# 1x9x1_2.net
KiCad netlist of a schematic drawn in Altium Designer
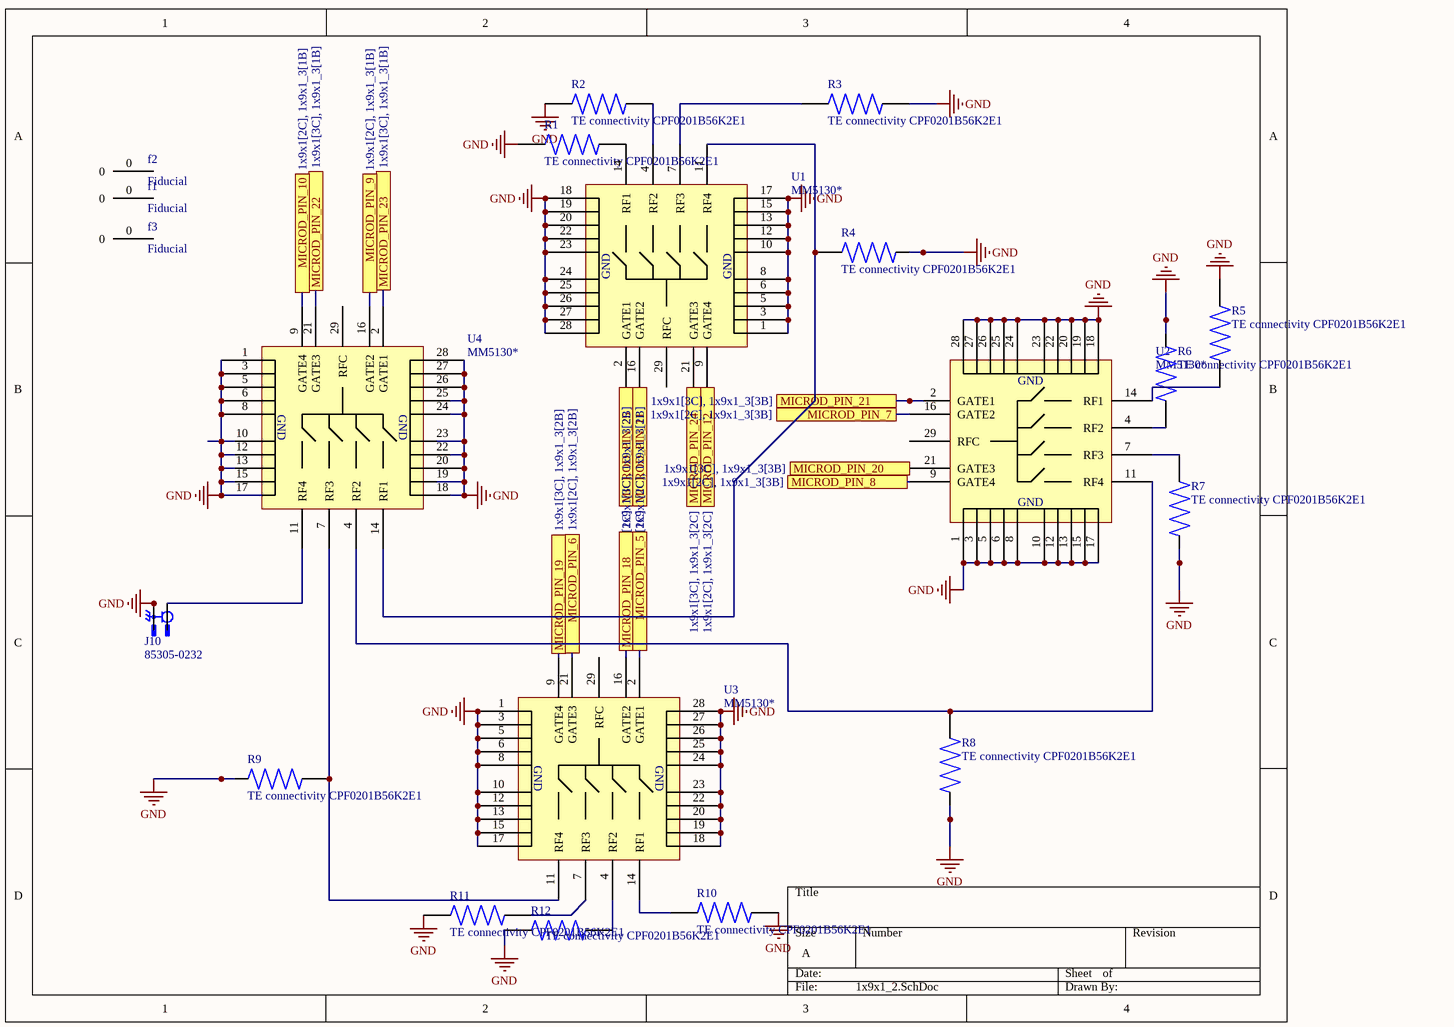
[diagram p0: 1x9x1_2.SchDoc]

(export (version "E")
  (design (tool "Eeschema 10.0.6"))
  (components
    (comp (ref "f1") (value "Fiducial") (footprint "fiducial") (libsource (lib "Fiducial") (part "Fiducial")))
    (comp (ref "f2") (value "Fiducial") (footprint "fiducial") (libsource (lib "Fiducial") (part "Fiducial")))
    (comp (ref "f3") (value "Fiducial") (footprint "fiducial") (libsource (lib "Fiducial") (part "Fiducial")))
    (comp (ref "J10")
      (value "85305-0232")
      (footprint "MOLEX_85305-0232")
      (description "SMP Connector Plug, Male Pin 50Ohm Surface Mount Solder")
      (fields (field (name "MP") "853050232") (field (name "MF") "Molex"))
      (libsource (lib "85305-0232") (part "85305-0232"))
    )
    (comp (ref "R1")
      (value "TE connectivity CPF0201B56K2E1")
      (footprint "0201-resistor")
      (description "CPF 0201 56K2 0.1% 25PPM 1K RL")
      (fields (field (name "MP") "ERJ1GN0R00C") (field (name "MFGR PART NO.") "CPF0201B56K2E1"))
      (libsource (lib "SchlibLafe") (part "TE connectivity CPF0201B56K2E1"))
    )
    (comp (ref "R2")
      (value "TE connectivity CPF0201B56K2E1")
      (footprint "0201-resistor")
      (description "CPF 0201 56K2 0.1% 25PPM 1K RL")
      (fields (field (name "MP") "ERJ1GN0R00C") (field (name "MFGR PART NO.") "CPF0201B56K2E1"))
      (libsource (lib "SchlibLafe") (part "TE connectivity CPF0201B56K2E1"))
    )
    (comp (ref "R3")
      (value "TE connectivity CPF0201B56K2E1")
      (footprint "0201-resistor")
      (description "CPF 0201 56K2 0.1% 25PPM 1K RL")
      (fields (field (name "MP") "ERJ1GN0R00C") (field (name "MFGR PART NO.") "CPF0201B56K2E1"))
      (libsource (lib "SchlibLafe") (part "TE connectivity CPF0201B56K2E1"))
    )
    (comp (ref "R4")
      (value "TE connectivity CPF0201B56K2E1")
      (footprint "0201-resistor")
      (description "CPF 0201 56K2 0.1% 25PPM 1K RL")
      (fields (field (name "MP") "ERJ1GN0R00C") (field (name "MFGR PART NO.") "CPF0201B56K2E1"))
      (libsource (lib "SchlibLafe") (part "TE connectivity CPF0201B56K2E1"))
    )
    (comp (ref "R5")
      (value "TE connectivity CPF0201B56K2E1")
      (footprint "0201-resistor")
      (description "CPF 0201 56K2 0.1% 25PPM 1K RL")
      (fields (field (name "MP") "ERJ1GN0R00C") (field (name "MFGR PART NO.") "CPF0201B56K2E1"))
      (libsource (lib "SchlibLafe") (part "TE connectivity CPF0201B56K2E1"))
    )
    (comp (ref "R6")
      (value "TE connectivity CPF0201B56K2E1")
      (footprint "0201-resistor")
      (description "CPF 0201 56K2 0.1% 25PPM 1K RL")
      (fields (field (name "MP") "ERJ1GN0R00C") (field (name "MFGR PART NO.") "CPF0201B56K2E1"))
      (libsource (lib "SchlibLafe") (part "TE connectivity CPF0201B56K2E1"))
    )
    (comp (ref "R7")
      (value "TE connectivity CPF0201B56K2E1")
      (footprint "0201-resistor")
      (description "CPF 0201 56K2 0.1% 25PPM 1K RL")
      (fields (field (name "MP") "ERJ1GN0R00C") (field (name "MFGR PART NO.") "CPF0201B56K2E1"))
      (libsource (lib "SchlibLafe") (part "TE connectivity CPF0201B56K2E1"))
    )
    (comp (ref "R8")
      (value "TE connectivity CPF0201B56K2E1")
      (footprint "0201-resistor")
      (description "CPF 0201 56K2 0.1% 25PPM 1K RL")
      (fields (field (name "MP") "ERJ1GN0R00C") (field (name "MFGR PART NO.") "CPF0201B56K2E1"))
      (libsource (lib "SchlibLafe") (part "TE connectivity CPF0201B56K2E1"))
    )
    (comp (ref "R9")
      (value "TE connectivity CPF0201B56K2E1")
      (footprint "0201-resistor")
      (description "CPF 0201 56K2 0.1% 25PPM 1K RL")
      (fields (field (name "MP") "ERJ1GN0R00C") (field (name "MFGR PART NO.") "CPF0201B56K2E1"))
      (libsource (lib "SchlibLafe") (part "TE connectivity CPF0201B56K2E1"))
    )
    (comp (ref "R10")
      (value "TE connectivity CPF0201B56K2E1")
      (footprint "0201-resistor")
      (description "CPF 0201 56K2 0.1% 25PPM 1K RL")
      (fields (field (name "MP") "ERJ1GN0R00C") (field (name "MFGR PART NO.") "CPF0201B56K2E1"))
      (libsource (lib "SchlibLafe") (part "TE connectivity CPF0201B56K2E1"))
    )
    (comp (ref "R11")
      (value "TE connectivity CPF0201B56K2E1")
      (footprint "0201-resistor")
      (description "CPF 0201 56K2 0.1% 25PPM 1K RL")
      (fields (field (name "MP") "ERJ1GN0R00C") (field (name "MFGR PART NO.") "CPF0201B56K2E1"))
      (libsource (lib "SchlibLafe") (part "TE connectivity CPF0201B56K2E1"))
    )
    (comp (ref "R12")
      (value "TE connectivity CPF0201B56K2E1")
      (footprint "0201-resistor")
      (description "CPF 0201 56K2 0.1% 25PPM 1K RL")
      (fields (field (name "MP") "ERJ1GN0R00C") (field (name "MFGR PART NO.") "CPF0201B56K2E1"))
      (libsource (lib "SchlibLafe") (part "TE connectivity CPF0201B56K2E1"))
    )
    (comp (ref "U1")
      (value "MM5130*")
      (footprint "MM5130-NORM_PCB_NOFLOOD")
      (description "High power SP4T MEMs switch")
      (libsource (lib "") (part "IC-MM5130_1"))
    )
    (comp (ref "U2")
      (value "MM5130*")
      (footprint "MM5130-NORM_PCB_NOFLOOD")
      (description "High power SP4T MEMs switch")
      (libsource (lib "") (part "IC-MM5130_2"))
    )
    (comp (ref "U3")
      (value "MM5130*")
      (footprint "MM5130-NORM_PCB_NOFLOOD")
      (description "High power SP4T MEMs switch")
      (libsource (lib "MM5130_SCHSYM") (part "IC-MM5130"))
    )
    (comp (ref "U4")
      (value "MM5130*")
      (footprint "MM5130-NORM_PCB_NOFLOOD")
      (description "High power SP4T MEMs switch")
      (libsource (lib "MM5130_SCHSYM") (part "IC-MM5130"))
    )
  )
  (nets
    (net (code "1") (name "/MICROD_PIN_5") (class "Default")
      (node (ref "U3") (pin "2") (pinfunction "GATE1_2") (pintype "passive"))
    )
    (net (code "2") (name "/MICROD_PIN_6") (class "Default")
      (node (ref "U3") (pin "21") (pinfunction "GATE3_21") (pintype "passive"))
    )
    (net (code "3") (name "/MICROD_PIN_7") (class "Default")
      (node (ref "U2") (pin "16") (pinfunction "GATE2_16") (pintype "passive"))
    )
    (net (code "4") (name "/MICROD_PIN_8") (class "Default")
      (node (ref "U2") (pin "9") (pinfunction "GATE4_9") (pintype "passive"))
    )
    (net (code "5") (name "/MICROD_PIN_9") (class "Default")
      (node (ref "U4") (pin "16") (pinfunction "GATE2_16") (pintype "passive"))
    )
    (net (code "6") (name "/MICROD_PIN_10") (class "Default")
      (node (ref "U4") (pin "9") (pinfunction "GATE4_9") (pintype "passive"))
    )
    (net (code "7") (name "/MICROD_PIN_11") (class "Default")
      (node (ref "U1") (pin "16") (pinfunction "GATE2_16") (pintype "passive"))
    )
    (net (code "8") (name "/MICROD_PIN_12") (class "Default")
      (node (ref "U1") (pin "9") (pinfunction "GATE4_9") (pintype "passive"))
    )
    (net (code "9") (name "/MICROD_PIN_18") (class "Default")
      (node (ref "U3") (pin "16") (pinfunction "GATE2_16") (pintype "passive"))
    )
    (net (code "10") (name "/MICROD_PIN_19") (class "Default")
      (node (ref "U3") (pin "9") (pinfunction "GATE4_9") (pintype "passive"))
    )
    (net (code "11") (name "/MICROD_PIN_20") (class "Default")
      (node (ref "U2") (pin "21") (pinfunction "GATE3_21") (pintype "passive"))
    )
    (net (code "12") (name "/MICROD_PIN_21") (class "Default")
      (node (ref "U2") (pin "2") (pinfunction "GATE1_2") (pintype "passive"))
    )
    (net (code "13") (name "/MICROD_PIN_22") (class "Default")
      (node (ref "U4") (pin "21") (pinfunction "GATE3_21") (pintype "passive"))
    )
    (net (code "14") (name "/MICROD_PIN_23") (class "Default")
      (node (ref "U4") (pin "2") (pinfunction "GATE1_2") (pintype "passive"))
    )
    (net (code "15") (name "/MICROD_PIN_24") (class "Default")
      (node (ref "U1") (pin "21") (pinfunction "GATE3_21") (pintype "passive"))
    )
    (net (code "16") (name "/MICROD_PIN_25") (class "Default")
      (node (ref "U1") (pin "2") (pinfunction "GATE1_2") (pintype "passive"))
    )
    (net (code "17") (name "GND") (class "Default")
      (node (ref "J10") (pin "10") (pinfunction "2_10") (pintype "passive"))
      (node (ref "J10") (pin "11") (pinfunction "2_11") (pintype "passive"))
      (node (ref "J10") (pin "12") (pinfunction "2_12") (pintype "passive"))
      (node (ref "J10") (pin "13") (pinfunction "2_13") (pintype "passive"))
      (node (ref "J10") (pin "14") (pinfunction "2_14") (pintype "passive"))
      (node (ref "J10") (pin "15") (pinfunction "2_15") (pintype "passive"))
      (node (ref "J10") (pin "16") (pinfunction "2_16") (pintype "passive"))
      (node (ref "J10") (pin "17") (pinfunction "2_17") (pintype "passive"))
      (node (ref "J10") (pin "18") (pinfunction "2_18") (pintype "passive"))
      (node (ref "J10") (pin "2") (pinfunction "2_2") (pintype "passive"))
      (node (ref "J10") (pin "3") (pinfunction "2_3") (pintype "passive"))
      (node (ref "J10") (pin "4") (pinfunction "2_4") (pintype "passive"))
      (node (ref "J10") (pin "5") (pinfunction "2_5") (pintype "passive"))
      (node (ref "J10") (pin "6") (pinfunction "2_6") (pintype "passive"))
      (node (ref "J10") (pin "7") (pinfunction "2_7") (pintype "passive"))
      (node (ref "J10") (pin "8") (pinfunction "2_8") (pintype "passive"))
      (node (ref "J10") (pin "9") (pinfunction "2_9") (pintype "passive"))
      (node (ref "R1") (pin "1") (pinfunction "1_1") (pintype "passive"))
      (node (ref "R10") (pin "1") (pinfunction "1_1") (pintype "passive"))
      (node (ref "R11") (pin "1") (pinfunction "1_1") (pintype "passive"))
      (node (ref "R12") (pin "2") (pinfunction "2_2") (pintype "passive"))
      (node (ref "R2") (pin "2") (pinfunction "2_2") (pintype "passive"))
      (node (ref "R3") (pin "1") (pinfunction "1_1") (pintype "passive"))
      (node (ref "R4") (pin "1") (pinfunction "1_1") (pintype "passive"))
      (node (ref "R5") (pin "1") (pinfunction "1_1") (pintype "passive"))
      (node (ref "R6") (pin "1") (pinfunction "1_1") (pintype "passive"))
      (node (ref "R7") (pin "2") (pinfunction "2_2") (pintype "passive"))
      (node (ref "R8") (pin "2") (pinfunction "2_2") (pintype "passive"))
      (node (ref "R9") (pin "2") (pinfunction "2_2") (pintype "passive"))
      (node (ref "U1") (pin "1") (pinfunction "GND_1") (pintype "passive"))
      (node (ref "U1") (pin "10") (pinfunction "GND_10") (pintype "passive"))
      (node (ref "U1") (pin "12") (pinfunction "GND_12") (pintype "passive"))
      (node (ref "U1") (pin "13") (pinfunction "GND_13") (pintype "passive"))
      (node (ref "U1") (pin "15") (pinfunction "GND_15") (pintype "passive"))
      (node (ref "U1") (pin "17") (pinfunction "GND_17") (pintype "passive"))
      (node (ref "U1") (pin "18") (pinfunction "GND_18") (pintype "passive"))
      (node (ref "U1") (pin "19") (pinfunction "GND_19") (pintype "passive"))
      (node (ref "U1") (pin "20") (pinfunction "GND_20") (pintype "passive"))
      (node (ref "U1") (pin "22") (pinfunction "GND_22") (pintype "passive"))
      (node (ref "U1") (pin "23") (pinfunction "GND_23") (pintype "passive"))
      (node (ref "U1") (pin "24") (pinfunction "GND_24") (pintype "passive"))
      (node (ref "U1") (pin "25") (pinfunction "GND_25") (pintype "passive"))
      (node (ref "U1") (pin "26") (pinfunction "GND_26") (pintype "passive"))
      (node (ref "U1") (pin "27") (pinfunction "GND_27") (pintype "passive"))
      (node (ref "U1") (pin "28") (pinfunction "GND_28") (pintype "passive"))
      (node (ref "U1") (pin "3") (pinfunction "GND_3") (pintype "passive"))
      (node (ref "U1") (pin "5") (pinfunction "GND_5") (pintype "passive"))
      (node (ref "U1") (pin "6") (pinfunction "GND_6") (pintype "passive"))
      (node (ref "U1") (pin "8") (pinfunction "GND_8") (pintype "passive"))
      (node (ref "U2") (pin "1") (pinfunction "GND_1") (pintype "passive"))
      (node (ref "U2") (pin "10") (pinfunction "GND_10") (pintype "passive"))
      (node (ref "U2") (pin "12") (pinfunction "GND_12") (pintype "passive"))
      (node (ref "U2") (pin "13") (pinfunction "GND_13") (pintype "passive"))
      (node (ref "U2") (pin "15") (pinfunction "GND_15") (pintype "passive"))
      (node (ref "U2") (pin "17") (pinfunction "GND_17") (pintype "passive"))
      (node (ref "U2") (pin "18") (pinfunction "GND_18") (pintype "passive"))
      (node (ref "U2") (pin "19") (pinfunction "GND_19") (pintype "passive"))
      (node (ref "U2") (pin "20") (pinfunction "GND_20") (pintype "passive"))
      (node (ref "U2") (pin "22") (pinfunction "GND_22") (pintype "passive"))
      (node (ref "U2") (pin "23") (pinfunction "GND_23") (pintype "passive"))
      (node (ref "U2") (pin "24") (pinfunction "GND_24") (pintype "passive"))
      (node (ref "U2") (pin "25") (pinfunction "GND_25") (pintype "passive"))
      (node (ref "U2") (pin "26") (pinfunction "GND_26") (pintype "passive"))
      (node (ref "U2") (pin "27") (pinfunction "GND_27") (pintype "passive"))
      (node (ref "U2") (pin "28") (pinfunction "GND_28") (pintype "passive"))
      (node (ref "U2") (pin "3") (pinfunction "GND_3") (pintype "passive"))
      (node (ref "U2") (pin "5") (pinfunction "GND_5") (pintype "passive"))
      (node (ref "U2") (pin "6") (pinfunction "GND_6") (pintype "passive"))
      (node (ref "U2") (pin "8") (pinfunction "GND_8") (pintype "passive"))
      (node (ref "U3") (pin "1") (pinfunction "GND_1") (pintype "passive"))
      (node (ref "U3") (pin "10") (pinfunction "GND_10") (pintype "passive"))
      (node (ref "U3") (pin "12") (pinfunction "GND_12") (pintype "passive"))
      (node (ref "U3") (pin "13") (pinfunction "GND_13") (pintype "passive"))
      (node (ref "U3") (pin "15") (pinfunction "GND_15") (pintype "passive"))
      (node (ref "U3") (pin "17") (pinfunction "GND_17") (pintype "passive"))
      (node (ref "U3") (pin "18") (pinfunction "GND_18") (pintype "passive"))
      (node (ref "U3") (pin "19") (pinfunction "GND_19") (pintype "passive"))
      (node (ref "U3") (pin "20") (pinfunction "GND_20") (pintype "passive"))
      (node (ref "U3") (pin "22") (pinfunction "GND_22") (pintype "passive"))
      (node (ref "U3") (pin "23") (pinfunction "GND_23") (pintype "passive"))
      (node (ref "U3") (pin "24") (pinfunction "GND_24") (pintype "passive"))
      (node (ref "U3") (pin "25") (pinfunction "GND_25") (pintype "passive"))
      (node (ref "U3") (pin "26") (pinfunction "GND_26") (pintype "passive"))
      (node (ref "U3") (pin "27") (pinfunction "GND_27") (pintype "passive"))
      (node (ref "U3") (pin "28") (pinfunction "GND_28") (pintype "passive"))
      (node (ref "U3") (pin "3") (pinfunction "GND_3") (pintype "passive"))
      (node (ref "U3") (pin "5") (pinfunction "GND_5") (pintype "passive"))
      (node (ref "U3") (pin "6") (pinfunction "GND_6") (pintype "passive"))
      (node (ref "U3") (pin "8") (pinfunction "GND_8") (pintype "passive"))
      (node (ref "U4") (pin "1") (pinfunction "GND_1") (pintype "passive"))
      (node (ref "U4") (pin "10") (pinfunction "GND_10") (pintype "passive"))
      (node (ref "U4") (pin "12") (pinfunction "GND_12") (pintype "passive"))
      (node (ref "U4") (pin "13") (pinfunction "GND_13") (pintype "passive"))
      (node (ref "U4") (pin "15") (pinfunction "GND_15") (pintype "passive"))
      (node (ref "U4") (pin "17") (pinfunction "GND_17") (pintype "passive"))
      (node (ref "U4") (pin "18") (pinfunction "GND_18") (pintype "passive"))
      (node (ref "U4") (pin "19") (pinfunction "GND_19") (pintype "passive"))
      (node (ref "U4") (pin "20") (pinfunction "GND_20") (pintype "passive"))
      (node (ref "U4") (pin "22") (pinfunction "GND_22") (pintype "passive"))
      (node (ref "U4") (pin "23") (pinfunction "GND_23") (pintype "passive"))
      (node (ref "U4") (pin "24") (pinfunction "GND_24") (pintype "passive"))
      (node (ref "U4") (pin "25") (pinfunction "GND_25") (pintype "passive"))
      (node (ref "U4") (pin "26") (pinfunction "GND_26") (pintype "passive"))
      (node (ref "U4") (pin "27") (pinfunction "GND_27") (pintype "passive"))
      (node (ref "U4") (pin "28") (pinfunction "GND_28") (pintype "passive"))
      (node (ref "U4") (pin "3") (pinfunction "GND_3") (pintype "passive"))
      (node (ref "U4") (pin "5") (pinfunction "GND_5") (pintype "passive"))
      (node (ref "U4") (pin "6") (pinfunction "GND_6") (pintype "passive"))
      (node (ref "U4") (pin "8") (pinfunction "GND_8") (pintype "passive"))
    )
    (net (code "18") (name "Net-(U1-RF1)") (class "Default")
      (node (ref "R1") (pin "2") (pinfunction "2_2") (pintype "passive"))
      (node (ref "U1") (pin "14") (pinfunction "RF1_14") (pintype "passive"))
    )
    (net (code "19") (name "Net-(U1-RF2)") (class "Default")
      (node (ref "R2") (pin "1") (pinfunction "1_1") (pintype "passive"))
      (node (ref "U1") (pin "4") (pinfunction "RF2_4") (pintype "passive"))
    )
    (net (code "20") (name "Net-(U1-RF3)") (class "Default")
      (node (ref "R3") (pin "2") (pinfunction "2_2") (pintype "passive"))
      (node (ref "U1") (pin "7") (pinfunction "RF3_7") (pintype "passive"))
    )
    (net (code "21") (name "Net-(U1-RF4)") (class "Default")
      (node (ref "R4") (pin "2") (pinfunction "2_2") (pintype "passive"))
      (node (ref "U1") (pin "11") (pinfunction "RF4_11") (pintype "passive"))
      (node (ref "U4") (pin "14") (pinfunction "RF1_14") (pintype "passive"))
    )
    (net (code "22") (name "Net-(U2-RF1)") (class "Default")
      (node (ref "R5") (pin "2") (pinfunction "2_2") (pintype "passive"))
      (node (ref "U2") (pin "14") (pinfunction "RF1_14") (pintype "passive"))
    )
    (net (code "23") (name "Net-(U2-RF2)") (class "Default")
      (node (ref "R6") (pin "2") (pinfunction "2_2") (pintype "passive"))
      (node (ref "U2") (pin "4") (pinfunction "RF2_4") (pintype "passive"))
    )
    (net (code "24") (name "Net-(U2-RF3)") (class "Default")
      (node (ref "R7") (pin "1") (pinfunction "1_1") (pintype "passive"))
      (node (ref "U2") (pin "7") (pinfunction "RF3_7") (pintype "passive"))
    )
    (net (code "25") (name "Net-(U2-RF4)") (class "Default")
      (node (ref "R8") (pin "1") (pinfunction "1_1") (pintype "passive"))
      (node (ref "U2") (pin "11") (pinfunction "RF4_11") (pintype "passive"))
      (node (ref "U4") (pin "4") (pinfunction "RF2_4") (pintype "passive"))
    )
    (net (code "26") (name "Net-(U3-RF1)") (class "Default")
      (node (ref "R10") (pin "2") (pinfunction "2_2") (pintype "passive"))
      (node (ref "U3") (pin "14") (pinfunction "RF1_14") (pintype "passive"))
    )
    (net (code "27") (name "Net-(U3-RF2)") (class "Default")
      (node (ref "R12") (pin "1") (pinfunction "1_1") (pintype "passive"))
      (node (ref "U3") (pin "4") (pinfunction "RF2_4") (pintype "passive"))
    )
    (net (code "28") (name "Net-(U3-RF3)") (class "Default")
      (node (ref "R11") (pin "2") (pinfunction "2_2") (pintype "passive"))
      (node (ref "U3") (pin "7") (pinfunction "RF3_7") (pintype "passive"))
    )
    (net (code "29") (name "Net-(U3-RF4)") (class "Default")
      (node (ref "R9") (pin "1") (pinfunction "1_1") (pintype "passive"))
      (node (ref "U3") (pin "11") (pinfunction "RF4_11") (pintype "passive"))
      (node (ref "U4") (pin "7") (pinfunction "RF3_7") (pintype "passive"))
    )
    (net (code "30") (name "Net-(U4-RF4)") (class "Default")
      (node (ref "J10") (pin "1") (pinfunction "1_1") (pintype "passive"))
      (node (ref "U4") (pin "11") (pinfunction "RF4_11") (pintype "passive"))
    )
    (net (code "31") (name "unconnected-(U1-RFC-Pad29)") (class "Default")
      (node (ref "U1") (pin "29") (pinfunction "RFC_29") (pintype "passive"))
    )
    (net (code "32") (name "unconnected-(U2-RFC-Pad29)") (class "Default")
      (node (ref "U2") (pin "29") (pinfunction "RFC_29") (pintype "passive"))
    )
    (net (code "33") (name "unconnected-(U3-RFC-Pad29)") (class "Default")
      (node (ref "U3") (pin "29") (pinfunction "RFC_29") (pintype "passive"))
    )
    (net (code "34") (name "unconnected-(U4-RFC-Pad29)") (class "Default")
      (node (ref "U4") (pin "29") (pinfunction "RFC_29") (pintype "passive"))
    )
    (net (code "35") (name "unconnected-(f1-Pad0)") (class "Default")
      (node (ref "f1") (pin "0") (pinfunction "0_0") (pintype "passive"))
    )
    (net (code "36") (name "unconnected-(f2-Pad0)") (class "Default")
      (node (ref "f2") (pin "0") (pinfunction "0_0") (pintype "passive"))
    )
    (net (code "37") (name "unconnected-(f3-Pad0)") (class "Default")
      (node (ref "f3") (pin "0") (pinfunction "0_0") (pintype "passive"))
    )
  )
)
